# MCU_POWER.net
KiCad netlist of a schematic drawn in Altium Designer
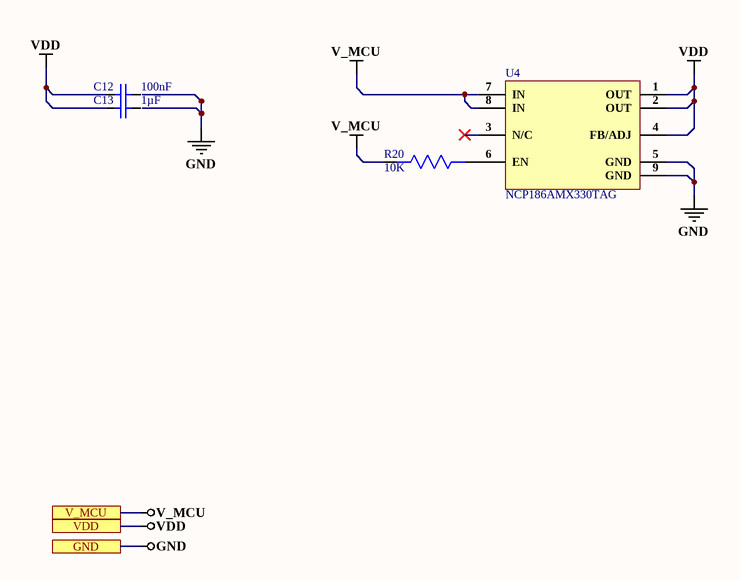
[diagram p0: MCU_POWER.SchDoc]

(export (version "E")
  (design (tool "Eeschema 10.0.6"))
  (components
    (comp (ref "C12")
      (value "100nF")
      (footprint "Cap0402")
      (description "CAP CER 0.1UF 25V X7R 0402")
      (fields
        (field (name "MANUFACTURER") "Yageo")
        (field (name "MANUFACTURER PART NUMBER") "CC0402KRX7R8BB104")
      )
      (libsource (lib "TT_IntLib") (part "CC0402KRX7R8BB104"))
    )
    (comp (ref "C13")
      (value "1µF")
      (footprint "Cap0402")
      (description "CAP CER 1UF 25V X5R 0402")
      (fields
        (field (name "MANUFACTURER") "Murata")
        (field (name "MANUFACTURER PART NUMBER") "GRM155R61E105KA12D")
      )
      (libsource (lib "TT_IntLib") (part "GRM155R61E105KA12D"))
    )
    (comp (ref "R20")
      (value "10K")
      (footprint "Res-0201")
      (description "GENERAL 0201 11% REEL (7INCH)")
      (fields
        (field (name "MANUFACTURER") "Yageo")
        (field (name "MANUFACTURER PART NUMBER") "RC0201FR-0710KL")
      )
      (libsource (lib "TT_IntLib") (part "RC0201FR-0710KL"))
    )
    (comp (ref "U4")
      (value "NCP186AMX330TAG")
      (footprint "NCP186AMX330TAG")
      (description "IC REG LINEAR 3.3V 1A 8XDFN")
      (fields (field (name "MANUFACTURER") "ON Semiconductor"))
      (libsource (lib "TT_IntLib") (part "NCP186AMX330TAG"))
    )
  )
  (nets
    (net (code "1") (name "GND") (class "Default")
      (node (ref "U4") (pin "5") (pinfunction "GND_5") (pintype "power_in"))
      (node (ref "U4") (pin "9") (pinfunction "GND_9") (pintype "power_in"))
    )
    (net (code "2") (name "Net-(U4-EN)") (class "Default")
      (node (ref "R20") (pin "1") (pintype "passive"))
      (node (ref "U4") (pin "6") (pinfunction "EN_6") (pintype "passive"))
    )
    (net (code "3") (name "VDD") (class "Default")
      (node (ref "C12") (pin "2") (pintype "passive"))
      (node (ref "C13") (pin "2") (pintype "passive"))
      (node (ref "U4") (pin "1") (pinfunction "OUT_1") (pintype "passive"))
      (node (ref "U4") (pin "2") (pinfunction "OUT_2") (pintype "passive"))
      (node (ref "U4") (pin "4") (pinfunction "FB/ADJ_4") (pintype "passive"))
    )
    (net (code "4") (name "V_MCU") (class "Default")
      (node (ref "R20") (pin "2") (pintype "passive"))
      (node (ref "U4") (pin "7") (pinfunction "IN_7") (pintype "passive"))
      (node (ref "U4") (pin "8") (pinfunction "IN_8") (pintype "passive"))
    )
    (net (code "5") (name "unconnected-(C12-Pad1)") (class "Default")
      (node (ref "C12") (pin "1") (pintype "passive"))
    )
    (net (code "6") (name "unconnected-(C13-Pad1)") (class "Default")
      (node (ref "C13") (pin "1") (pintype "passive"))
    )
    (net (code "7") (name "unconnected-(U4-N{slash}C-Pad3)") (class "Default")
      (node (ref "U4") (pin "3") (pinfunction "N/C_3") (pintype "passive+no_connect"))
    )
  )
)
